# artboat_rev_b.net
KiCad netlist of a schematic drawn in EAGLE
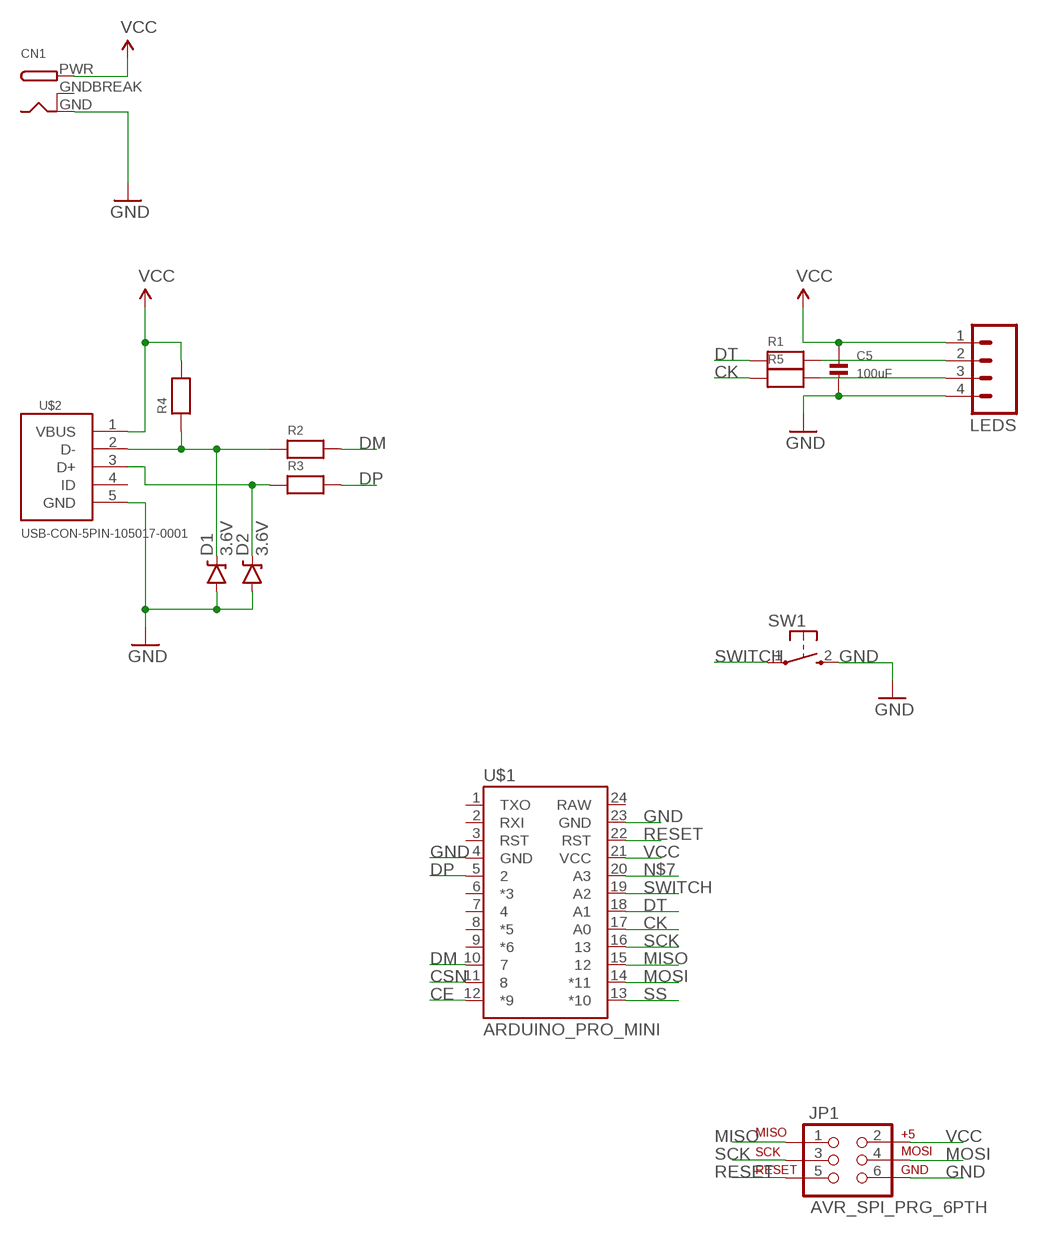
[diagram p0: schematic, sheet 1]

(export (version "E")
  (design (tool "Eeschema 10.0.6"))
  (components
    (comp (ref "C5")
      (value "100uF")
      (footprint "eagle-import:1206")
      (libsource (lib "eagle-import") (part "CAP_CERAMIC1206"))
    )
    (comp (ref "CN1")
      (value "DCBARRELPTH")
      (footprint "eagle-import:DCJACK_2MM_PTH")
      (libsource (lib "eagle-import") (part "DCBARRELPTH"))
    )
    (comp (ref "D1")
      (value "3.6V")
      (footprint "eagle-import:SOD-323")
      (libsource (lib "eagle-import") (part "DIODE-ZENER3.6V"))
    )
    (comp (ref "D2")
      (value "3.6V")
      (footprint "eagle-import:SOD-323")
      (libsource (lib "eagle-import") (part "DIODE-ZENER3.6V"))
    )
    (comp (ref "JP1")
      (value "AVR_SPI_PRG_6PTH")
      (footprint "eagle-import:2X3")
      (libsource (lib "eagle-import") (part "AVR_SPI_PRG_6PTH"))
    )
    (comp (ref "LEDS")
      (value "M04PTH")
      (footprint "eagle-import:1X04")
      (libsource (lib "eagle-import") (part "M04PTH"))
    )
    (comp (ref "R1")
      (value "RESISTOR_0603")
      (footprint "eagle-import:_0603")
      (libsource (lib "eagle-import") (part "RESISTOR_0603"))
    )
    (comp (ref "R2")
      (value "RESISTOR_0603")
      (footprint "eagle-import:_0603")
      (libsource (lib "eagle-import") (part "RESISTOR_0603"))
    )
    (comp (ref "R3")
      (value "RESISTOR_0603")
      (footprint "eagle-import:_0603")
      (libsource (lib "eagle-import") (part "RESISTOR_0603"))
    )
    (comp (ref "R4")
      (value "RESISTOR_0603")
      (footprint "eagle-import:_0603")
      (libsource (lib "eagle-import") (part "RESISTOR_0603"))
    )
    (comp (ref "R5")
      (value "RESISTOR_0603")
      (footprint "eagle-import:_0603")
      (libsource (lib "eagle-import") (part "RESISTOR_0603"))
    )
    (comp (ref "SW1")
      (value "TACTILE-SWITCH-1825027")
      (footprint "eagle-import:1825027")
      (libsource (lib "eagle-import") (part "TACTILE-SWITCH-1825027"))
    )
    (comp (ref "U$1")
      (value "ARDUINO_PRO_MINI")
      (footprint "eagle-import:ARDUINO_PRO_MINI")
      (libsource (lib "eagle-import") (part "ARDUINO_PRO_MINI"))
    )
    (comp (ref "U$2")
      (value "USB-CON-5PIN-105017-0001")
      (footprint "eagle-import:USB-MICRO-MOLEX-105017-0001")
      (libsource (lib "eagle-import") (part "USB-CON-5PIN-105017-0001"))
    )
  )
  (nets
    (net (code "1") (name "/CE") (class "Default")
      (node (ref "U$1") (pin "12") (pinfunction "*9_12") (pintype "bidirectional"))
    )
    (net (code "2") (name "/CK") (class "Default")
      (node (ref "R5") (pin "1") (pinfunction "1_1") (pintype "passive"))
      (node (ref "U$1") (pin "17") (pinfunction "A0_17") (pintype "bidirectional"))
    )
    (net (code "3") (name "/CSN") (class "Default")
      (node (ref "U$1") (pin "11") (pinfunction "8_11") (pintype "bidirectional"))
    )
    (net (code "4") (name "/DM") (class "Default")
      (node (ref "R2") (pin "2") (pinfunction "2_2") (pintype "passive"))
      (node (ref "U$1") (pin "10") (pinfunction "7_10") (pintype "bidirectional"))
    )
    (net (code "5") (name "/DP") (class "Default")
      (node (ref "R3") (pin "2") (pinfunction "2_2") (pintype "passive"))
      (node (ref "U$1") (pin "5") (pinfunction "2_5") (pintype "bidirectional"))
    )
    (net (code "6") (name "/DT") (class "Default")
      (node (ref "R1") (pin "1") (pinfunction "1_1") (pintype "passive"))
      (node (ref "U$1") (pin "18") (pinfunction "A1_18") (pintype "bidirectional"))
    )
    (net (code "7") (name "/GNDBREAK") (class "Default")
      (node (ref "CN1") (pin "GNDBREAK") (pinfunction "GNDBREAK_GNDBREAK") (pintype "power_in"))
    )
    (net (code "8") (name "/MISO") (class "Default")
      (node (ref "JP1") (pin "1") (pinfunction "1_1") (pintype "passive"))
      (node (ref "U$1") (pin "15") (pinfunction "12_15") (pintype "bidirectional"))
    )
    (net (code "9") (name "/MOSI") (class "Default")
      (node (ref "JP1") (pin "4") (pinfunction "4_4") (pintype "passive"))
      (node (ref "U$1") (pin "14") (pinfunction "*11_14") (pintype "bidirectional"))
    )
    (net (code "10") (name "/N$7") (class "Default")
      (node (ref "U$1") (pin "20") (pinfunction "A3_20") (pintype "bidirectional"))
    )
    (net (code "11") (name "/RESET") (class "Default")
      (node (ref "JP1") (pin "5") (pinfunction "5_5") (pintype "passive"))
      (node (ref "U$1") (pin "22") (pinfunction "RST_22") (pintype "bidirectional"))
    )
    (net (code "12") (name "/SCK") (class "Default")
      (node (ref "JP1") (pin "3") (pinfunction "3_3") (pintype "passive"))
      (node (ref "U$1") (pin "16") (pinfunction "13_16") (pintype "bidirectional"))
    )
    (net (code "13") (name "/SS") (class "Default")
      (node (ref "U$1") (pin "13") (pinfunction "*10_13") (pintype "bidirectional"))
    )
    (net (code "14") (name "/SWITCH") (class "Default")
      (node (ref "SW1") (pin "1") (pinfunction "1_1") (pintype "passive"))
      (node (ref "U$1") (pin "19") (pinfunction "A2_19") (pintype "bidirectional"))
    )
    (net (code "15") (name "GND") (class "Default")
      (node (ref "C5") (pin "2") (pinfunction "P$2_2") (pintype "passive"))
      (node (ref "CN1") (pin "GND") (pinfunction "GND_GND") (pintype "power_in"))
      (node (ref "D1") (pin "A") (pinfunction "A_A") (pintype "passive"))
      (node (ref "D2") (pin "A") (pinfunction "A_A") (pintype "passive"))
      (node (ref "JP1") (pin "6") (pinfunction "6_6") (pintype "passive"))
      (node (ref "LEDS") (pin "4") (pinfunction "4_4") (pintype "passive"))
      (node (ref "SW1") (pin "2") (pinfunction "3_2") (pintype "passive"))
      (node (ref "U$1") (pin "23") (pinfunction "GND_23") (pintype "bidirectional"))
      (node (ref "U$1") (pin "4") (pinfunction "GND_4") (pintype "bidirectional"))
      (node (ref "U$2") (pin "5") (pinfunction "GND_5") (pintype "power_in"))
    )
    (net (code "16") (name "Net-(LEDS-Pad2)") (class "Default")
      (node (ref "LEDS") (pin "2") (pinfunction "2_2") (pintype "passive"))
      (node (ref "R1") (pin "2") (pinfunction "2_2") (pintype "passive"))
    )
    (net (code "17") (name "Net-(LEDS-Pad3)") (class "Default")
      (node (ref "LEDS") (pin "3") (pinfunction "3_3") (pintype "passive"))
      (node (ref "R5") (pin "2") (pinfunction "2_2") (pintype "passive"))
    )
    (net (code "18") (name "Net-(U$2-D+)") (class "Default")
      (node (ref "D2") (pin "C") (pinfunction "C_C") (pintype "passive"))
      (node (ref "R3") (pin "1") (pinfunction "1_1") (pintype "passive"))
      (node (ref "U$2") (pin "3") (pinfunction "D+_3") (pintype "bidirectional"))
    )
    (net (code "19") (name "Net-(U$2-D-)") (class "Default")
      (node (ref "D1") (pin "C") (pinfunction "C_C") (pintype "passive"))
      (node (ref "R2") (pin "1") (pinfunction "1_1") (pintype "passive"))
      (node (ref "R4") (pin "1") (pinfunction "1_1") (pintype "passive"))
      (node (ref "U$2") (pin "2") (pinfunction "D-_2") (pintype "bidirectional"))
    )
    (net (code "20") (name "VCC") (class "Default")
      (node (ref "C5") (pin "1") (pinfunction "P$1_1") (pintype "passive"))
      (node (ref "CN1") (pin "PWR") (pinfunction "PWR_PWR") (pintype "power_in"))
      (node (ref "JP1") (pin "2") (pinfunction "2_2") (pintype "passive"))
      (node (ref "LEDS") (pin "1") (pinfunction "1_1") (pintype "passive"))
      (node (ref "R4") (pin "2") (pinfunction "2_2") (pintype "passive"))
      (node (ref "U$1") (pin "21") (pinfunction "VCC_21") (pintype "bidirectional"))
      (node (ref "U$2") (pin "1") (pinfunction "VBUS_1") (pintype "power_in"))
    )
    (net (code "21") (name "unconnected-(U$1-*3-Pad6)") (class "Default")
      (node (ref "U$1") (pin "6") (pinfunction "*3_6") (pintype "bidirectional"))
    )
    (net (code "22") (name "unconnected-(U$1-*5-Pad8)") (class "Default")
      (node (ref "U$1") (pin "8") (pinfunction "*5_8") (pintype "bidirectional"))
    )
    (net (code "23") (name "unconnected-(U$1-*6-Pad9)") (class "Default")
      (node (ref "U$1") (pin "9") (pinfunction "*6_9") (pintype "bidirectional"))
    )
    (net (code "24") (name "unconnected-(U$1-4-Pad7)") (class "Default")
      (node (ref "U$1") (pin "7") (pinfunction "4_7") (pintype "bidirectional"))
    )
    (net (code "25") (name "unconnected-(U$1-RAW-Pad24)") (class "Default")
      (node (ref "U$1") (pin "24") (pinfunction "RAW_24") (pintype "bidirectional"))
    )
    (net (code "26") (name "unconnected-(U$1-RST-Pad3)") (class "Default")
      (node (ref "U$1") (pin "3") (pinfunction "RST_3") (pintype "bidirectional"))
    )
    (net (code "27") (name "unconnected-(U$1-RXI-Pad2)") (class "Default")
      (node (ref "U$1") (pin "2") (pinfunction "RXI_2") (pintype "bidirectional"))
    )
    (net (code "28") (name "unconnected-(U$1-TXO-Pad1)") (class "Default")
      (node (ref "U$1") (pin "1") (pinfunction "TXO_1") (pintype "bidirectional"))
    )
    (net (code "29") (name "unconnected-(U$2-ID-Pad4)") (class "Default")
      (node (ref "U$2") (pin "4") (pinfunction "ID_4") (pintype "bidirectional"))
    )
  )
)
